# Power.net
KiCad netlist of a schematic drawn in Altium Designer
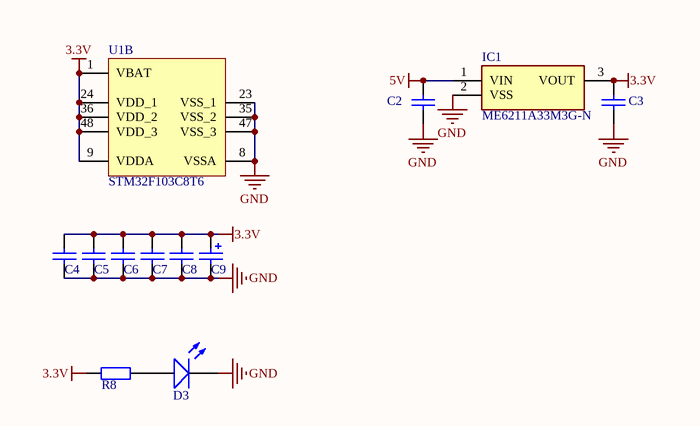
[diagram p0: Power.SchDoc]

(export (version "E")
  (design (tool "Eeschema 10.0.6"))
  (components
    (comp (ref "C2")
      (value "1uF")
      (footprint "CAP-0603")
      (description "贴片电容")
      (libsource (lib "Power_Lib_Altium") (part "CAP"))
    )
    (comp (ref "C3")
      (value "1uF")
      (footprint "CAP-0603")
      (description "贴片电容")
      (libsource (lib "Power_Lib_Altium") (part "CAP"))
    )
    (comp (ref "C4")
      (value "100nF")
      (footprint "CAP-0603")
      (description "贴片电容")
      (libsource (lib "Power_Lib_Altium") (part "CAP"))
    )
    (comp (ref "C5")
      (value "100nF")
      (footprint "CAP-0603")
      (description "贴片电容")
      (libsource (lib "Power_Lib_Altium") (part "CAP"))
    )
    (comp (ref "C6")
      (value "100nF")
      (footprint "CAP-0603")
      (description "贴片电容")
      (libsource (lib "Power_Lib_Altium") (part "CAP"))
    )
    (comp (ref "C7")
      (value "100nF")
      (footprint "CAP-0603")
      (description "贴片电容")
      (libsource (lib "Power_Lib_Altium") (part "CAP"))
    )
    (comp (ref "C8")
      (value "100nF")
      (footprint "CAP-0603")
      (description "贴片电容")
      (libsource (lib "Power_Lib_Altium") (part "CAP"))
    )
    (comp (ref "C9")
      (value "10uF")
      (footprint "CASE-B_3528")
      (description "贴片电容-有极性")
      (libsource (lib "Power_Lib_Altium") (part "CAP-POL"))
    )
    (comp (ref "D3")
      (value "RED")
      (footprint "LED-0603")
      (description "发光二极管")
      (libsource (lib "Power_Lib_Altium") (part "LED"))
    )
    (comp (ref "IC1")
      (value "ME6211A33M3G-N")
      (footprint "SOT-23-3")
      (description "线性稳压")
      (fields (field (name "MANUFACTURER_PART_NUMBER") "SI2302DS") (field (name "RS PART NUMBER") "7983053P"))
      (libsource (lib "Power_Lib_Altium") (part "ME6211A33M3G-N"))
    )
    (comp (ref "R8")
      (value "10K")
      (footprint "R-0603")
      (description "贴片电阻")
      (libsource (lib "Power_Lib_Altium") (part "RES"))
    )
    (comp (ref "U1")
      (value "STM32F103C8T6")
      (footprint "LQFP_48")
      (description "单片机")
      (fields (field (name "PARTNUMBER") "STM32F100C8T6B"))
      (libsource (lib "Power_Lib_Altium") (part "STM32F103Cx"))
    )
  )
  (nets
    (net (code "1") (name "3.3V") (class "Default")
      (node (ref "C3") (pin "2") (pinfunction "2_2") (pintype "passive"))
      (node (ref "C4") (pin "2") (pinfunction "2_2") (pintype "passive"))
      (node (ref "C5") (pin "2") (pinfunction "2_2") (pintype "passive"))
      (node (ref "C6") (pin "2") (pinfunction "2_2") (pintype "passive"))
      (node (ref "C7") (pin "2") (pinfunction "2_2") (pintype "passive"))
      (node (ref "C8") (pin "2") (pinfunction "2_2") (pintype "passive"))
      (node (ref "C9") (pin "1") (pinfunction "1_1") (pintype "passive"))
      (node (ref "IC1") (pin "3") (pinfunction "VOUT_3") (pintype "passive"))
      (node (ref "R8") (pin "2") (pinfunction "2_2") (pintype "passive"))
      (node (ref "U1") (pin "1") (pinfunction "VBAT_1") (pintype "power_in"))
      (node (ref "U1") (pin "24") (pinfunction "VDD_1_24") (pintype "power_in"))
      (node (ref "U1") (pin "36") (pinfunction "VDD_2_36") (pintype "power_in"))
      (node (ref "U1") (pin "48") (pinfunction "VDD_3_48") (pintype "power_in"))
      (node (ref "U1") (pin "9") (pinfunction "VDDA_9") (pintype "power_in"))
    )
    (net (code "2") (name "5V") (class "Default")
      (node (ref "C2") (pin "2") (pinfunction "2_2") (pintype "passive"))
      (node (ref "IC1") (pin "1") (pinfunction "VIN_1") (pintype "passive"))
    )
    (net (code "3") (name "GND") (class "Default")
      (node (ref "C2") (pin "1") (pinfunction "1_1") (pintype "passive"))
      (node (ref "C3") (pin "1") (pinfunction "1_1") (pintype "passive"))
      (node (ref "C4") (pin "1") (pinfunction "1_1") (pintype "passive"))
      (node (ref "C5") (pin "1") (pinfunction "1_1") (pintype "passive"))
      (node (ref "C6") (pin "1") (pinfunction "1_1") (pintype "passive"))
      (node (ref "C7") (pin "1") (pinfunction "1_1") (pintype "passive"))
      (node (ref "C8") (pin "1") (pinfunction "1_1") (pintype "passive"))
      (node (ref "C9") (pin "2") (pinfunction "2_2") (pintype "passive"))
      (node (ref "D3") (pin "K") (pinfunction "K_K") (pintype "passive"))
      (node (ref "IC1") (pin "2") (pinfunction "VSS_2") (pintype "passive"))
      (node (ref "U1") (pin "23") (pinfunction "VSS_1_23") (pintype "power_in"))
      (node (ref "U1") (pin "35") (pinfunction "VSS_2_35") (pintype "power_in"))
      (node (ref "U1") (pin "47") (pinfunction "VSS_3_47") (pintype "power_in"))
      (node (ref "U1") (pin "8") (pinfunction "VSSA_8") (pintype "power_in"))
    )
    (net (code "4") (name "Net-(D3-PadA)") (class "Default")
      (node (ref "D3") (pin "A") (pinfunction "A_A") (pintype "passive"))
      (node (ref "R8") (pin "1") (pinfunction "1_1") (pintype "passive"))
    )
  )
)
